# Temperature.net
KiCad netlist of a schematic drawn in EAGLE
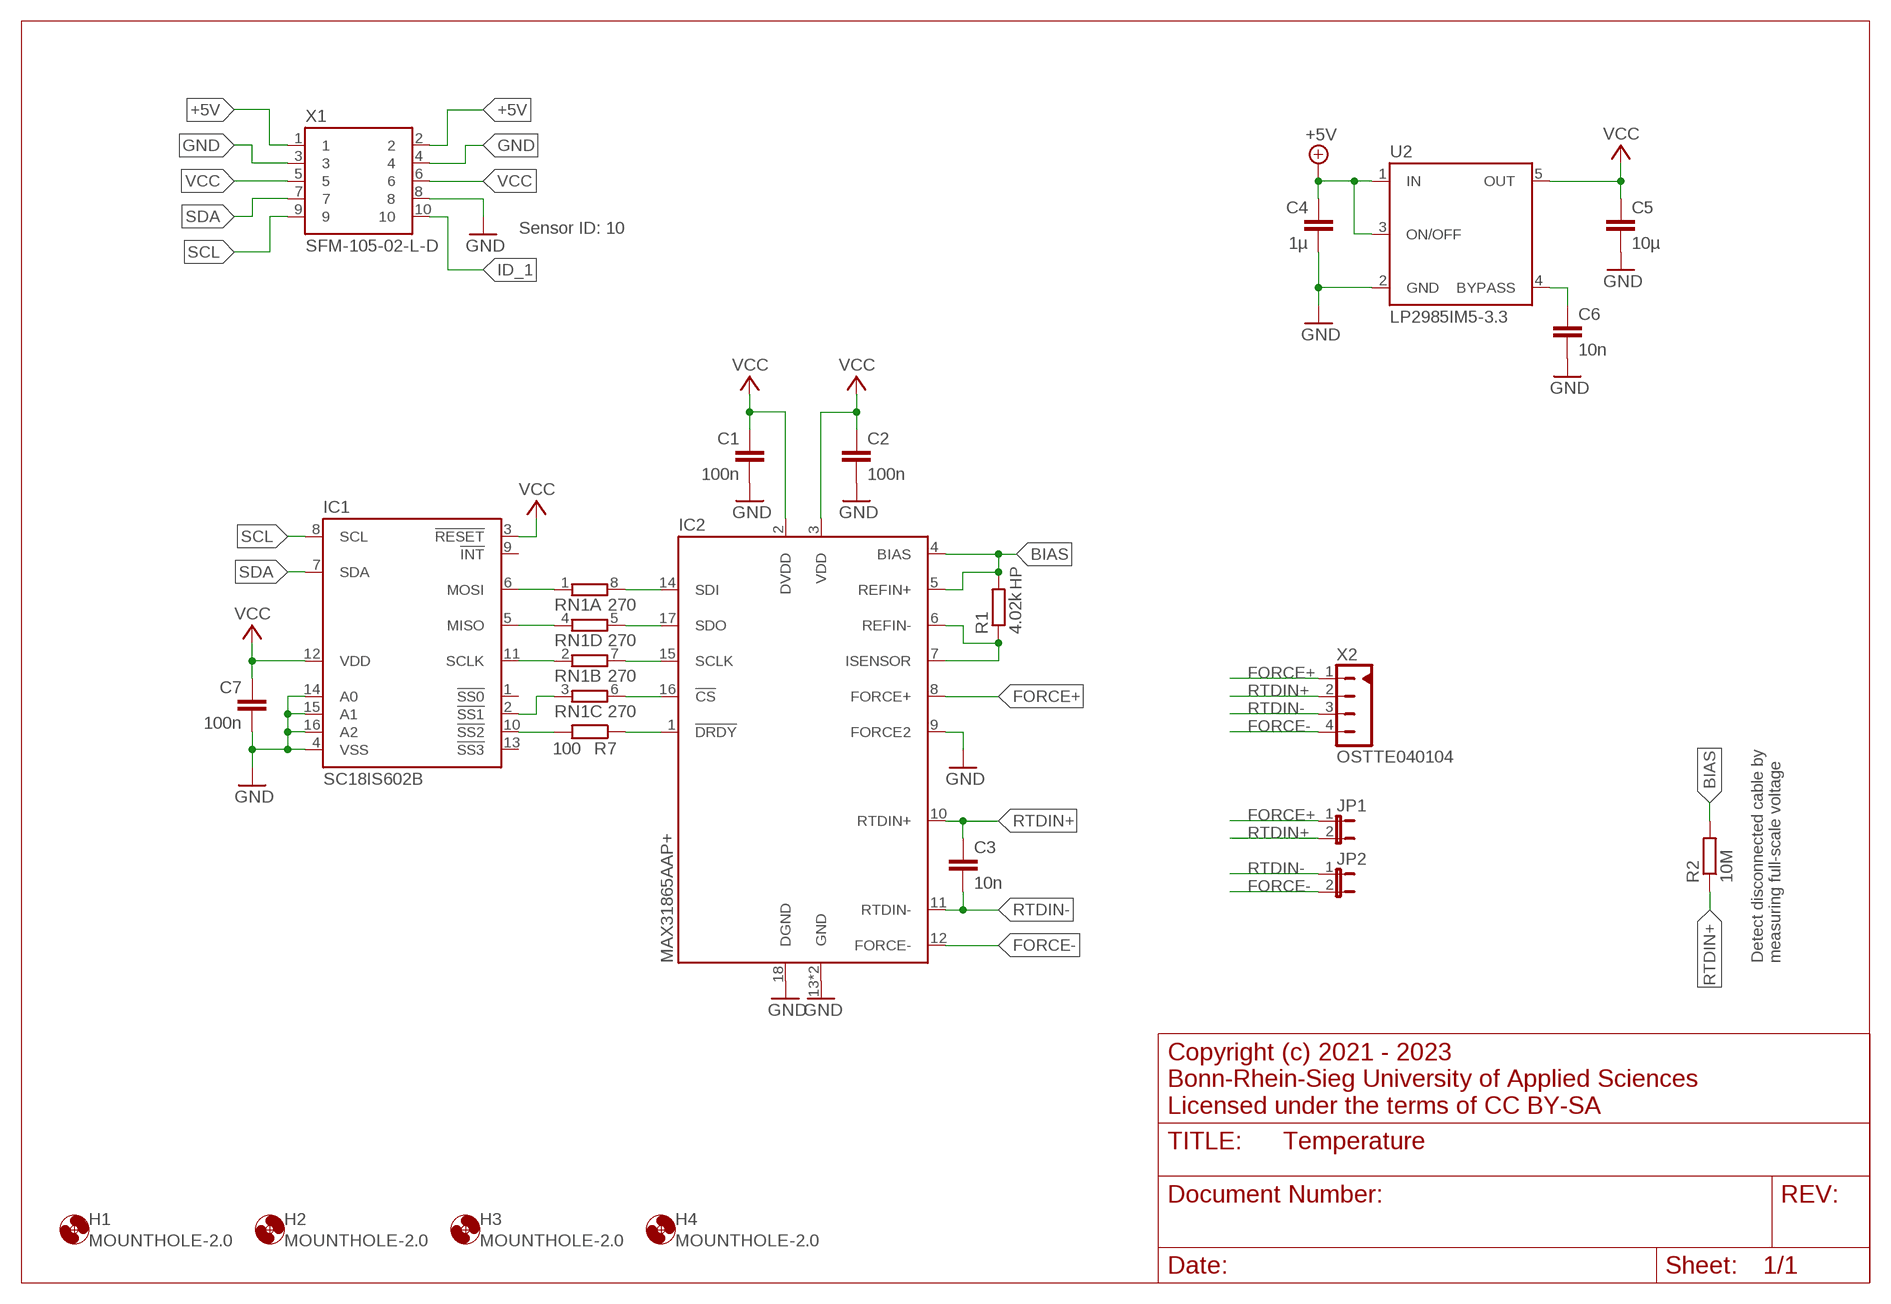
[diagram p0: schematic, sheet 1]

(export (version "E")
  (design (tool "Eeschema 10.0.6"))
  (components
    (comp (ref "C1")
      (value "100n")
      (footprint "eagle-import:C0603")
      (libsource (lib "eagle-import") (part "C-EUC0603"))
    )
    (comp (ref "C2")
      (value "100n")
      (footprint "eagle-import:C0603")
      (libsource (lib "eagle-import") (part "C-EUC0603"))
    )
    (comp (ref "C3")
      (value "10n")
      (footprint "eagle-import:C0603")
      (libsource (lib "eagle-import") (part "C-EUC0603"))
    )
    (comp (ref "C4")
      (value "1µ")
      (footprint "eagle-import:C0603")
      (libsource (lib "eagle-import") (part "C-EUC0603"))
    )
    (comp (ref "C5")
      (value "10µ")
      (footprint "eagle-import:C0603")
      (libsource (lib "eagle-import") (part "C-EUC0603"))
    )
    (comp (ref "C6")
      (value "10n")
      (footprint "eagle-import:C0603")
      (libsource (lib "eagle-import") (part "C-EUC0603"))
    )
    (comp (ref "C7")
      (value "100n")
      (footprint "eagle-import:C0603")
      (libsource (lib "eagle-import") (part "C-EUC0603"))
    )
    (comp (ref "H1")
      (value "MOUNTHOLE-2.0")
      (footprint "eagle-import:2.0")
      (libsource (lib "eagle-import") (part "MOUNTHOLE-2.0"))
    )
    (comp (ref "H2")
      (value "MOUNTHOLE-2.0")
      (footprint "eagle-import:2.0")
      (libsource (lib "eagle-import") (part "MOUNTHOLE-2.0"))
    )
    (comp (ref "H3")
      (value "MOUNTHOLE-2.0")
      (footprint "eagle-import:2.0")
      (libsource (lib "eagle-import") (part "MOUNTHOLE-2.0"))
    )
    (comp (ref "H4")
      (value "MOUNTHOLE-2.0")
      (footprint "eagle-import:2.0")
      (libsource (lib "eagle-import") (part "MOUNTHOLE-2.0"))
    )
    (comp (ref "IC1")
      (value "SC18IS602B")
      (footprint "eagle-import:TSSOP16")
      (libsource (lib "eagle-import") (part "SC18IS602B"))
    )
    (comp (ref "IC2")
      (value "MAX31865AAP+")
      (footprint "eagle-import:SSOP20")
      (libsource (lib "eagle-import") (part "MAX31865A?P+A"))
    )
    (comp (ref "JP1")
      (value "JP1E")
      (footprint "eagle-import:JP1")
      (libsource (lib "eagle-import") (part "JP1E"))
    )
    (comp (ref "JP2")
      (value "JP1E")
      (footprint "eagle-import:JP1")
      (libsource (lib "eagle-import") (part "JP1E"))
    )
    (comp (ref "R1")
      (value "4.02k")
      (footprint "eagle-import:R0603")
      (libsource (lib "eagle-import") (part "R-EU_R0603"))
    )
    (comp (ref "R2")
      (value "10M")
      (footprint "eagle-import:R0603")
      (libsource (lib "eagle-import") (part "R-EU_R0603"))
    )
    (comp (ref "R7")
      (value "100")
      (footprint "eagle-import:R0603")
      (libsource (lib "eagle-import") (part "R-EU_R0603"))
    )
    (comp (ref "RN1")
      (value "270")
      (footprint "eagle-import:EXB38V")
      (libsource (lib "eagle-import") (part "4R-NEXB38V"))
    )
    (comp (ref "U2")
      (value "LP2985IM5-3.3")
      (footprint "eagle-import:SOT23-5")
      (libsource (lib "eagle-import") (part "LP2985?-IM53.3"))
    )
    (comp (ref "X1")
      (value "SFM-105-02-L-D")
      (footprint "eagle-import:SAMTEC-SFM-105-02-L-D")
      (libsource (lib "eagle-import") (part "SFM-105-02-L-D"))
    )
    (comp (ref "X2")
      (value "OSTTE040104")
      (footprint "eagle-import:OSTTE04")
      (libsource (lib "eagle-import") (part "OSTTE040104"))
    )
  )
  (nets
    (net (code "1") (name "+5V") (class "Default")
      (node (ref "C4") (pin "1") (pinfunction "1_1") (pintype "passive"))
      (node (ref "U2") (pin "1") (pinfunction "IN_1") (pintype "bidirectional"))
      (node (ref "U2") (pin "3") (pinfunction "ON/OFF_3") (pintype "bidirectional"))
      (node (ref "X1") (pin "1") (pinfunction "1_1") (pintype "passive"))
      (node (ref "X1") (pin "2") (pinfunction "2_2") (pintype "passive"))
    )
    (net (code "2") (name "BIAS") (class "Default")
      (node (ref "IC2") (pin "4") (pinfunction "BIAS_4") (pintype "bidirectional"))
      (node (ref "IC2") (pin "5") (pinfunction "REFIN+_5") (pintype "bidirectional"))
      (node (ref "R1") (pin "2") (pinfunction "2_2") (pintype "passive"))
      (node (ref "R2") (pin "2") (pinfunction "2_2") (pintype "passive"))
    )
    (net (code "3") (name "FORCE+") (class "Default")
      (node (ref "IC2") (pin "8") (pinfunction "FORCE+_8") (pintype "bidirectional"))
      (node (ref "JP1") (pin "1") (pinfunction "1_1") (pintype "passive"))
      (node (ref "X2") (pin "1") (pinfunction "1_1") (pintype "passive"))
    )
    (net (code "4") (name "FORCE-") (class "Default")
      (node (ref "IC2") (pin "12") (pinfunction "FORCE-_12") (pintype "bidirectional"))
      (node (ref "JP2") (pin "2") (pinfunction "2_2") (pintype "passive"))
      (node (ref "X2") (pin "4") (pinfunction "4_4") (pintype "passive"))
    )
    (net (code "5") (name "GND") (class "Default")
      (node (ref "C1") (pin "2") (pinfunction "2_2") (pintype "passive"))
      (node (ref "C2") (pin "2") (pinfunction "2_2") (pintype "passive"))
      (node (ref "C4") (pin "2") (pinfunction "2_2") (pintype "passive"))
      (node (ref "C5") (pin "2") (pinfunction "2_2") (pintype "passive"))
      (node (ref "C6") (pin "2") (pinfunction "2_2") (pintype "passive"))
      (node (ref "C7") (pin "2") (pinfunction "2_2") (pintype "passive"))
      (node (ref "IC1") (pin "14") (pinfunction "A0_14") (pintype "input"))
      (node (ref "IC1") (pin "15") (pinfunction "A1_15") (pintype "input"))
      (node (ref "IC1") (pin "16") (pinfunction "A2_16") (pintype "input"))
      (node (ref "IC1") (pin "4") (pinfunction "VSS_4") (pintype "power_in"))
      (node (ref "IC2") (pin "13") (pinfunction "GND_13") (pintype "bidirectional"))
      (node (ref "IC2") (pin "18") (pinfunction "DGND_18") (pintype "bidirectional"))
      (node (ref "IC2") (pin "19") (pinfunction "GND_19") (pintype "bidirectional"))
      (node (ref "IC2") (pin "9") (pinfunction "FORCE2_9") (pintype "bidirectional"))
      (node (ref "U2") (pin "2") (pinfunction "GND_2") (pintype "bidirectional"))
      (node (ref "X1") (pin "3") (pinfunction "3_3") (pintype "passive"))
      (node (ref "X1") (pin "4") (pinfunction "4_4") (pintype "passive"))
      (node (ref "X1") (pin "8") (pinfunction "8_8") (pintype "passive"))
    )
    (net (code "6") (name "ID_1") (class "Default")
      (node (ref "X1") (pin "10") (pinfunction "10_10") (pintype "passive"))
    )
    (net (code "7") (name "Net-(IC1-MISO)") (class "Default")
      (node (ref "IC1") (pin "5") (pinfunction "MISO_5") (pintype "input"))
      (node (ref "RN1") (pin "4") (pinfunction "1_4") (pintype "passive"))
    )
    (net (code "8") (name "Net-(IC1-MOSI)") (class "Default")
      (node (ref "IC1") (pin "6") (pinfunction "MOSI_6") (pintype "output"))
      (node (ref "RN1") (pin "1") (pinfunction "1_1") (pintype "passive"))
    )
    (net (code "9") (name "Net-(IC1-SCLK)") (class "Default")
      (node (ref "IC1") (pin "11") (pinfunction "SCLK_11") (pintype "output"))
      (node (ref "RN1") (pin "2") (pinfunction "1_2") (pintype "passive"))
    )
    (net (code "10") (name "Net-(IC1-~{SS1})") (class "Default")
      (node (ref "IC1") (pin "2") (pinfunction "~{SS1}_2") (pintype "bidirectional"))
      (node (ref "RN1") (pin "3") (pinfunction "1_3") (pintype "passive"))
    )
    (net (code "11") (name "Net-(IC1-~{SS2})") (class "Default")
      (node (ref "IC1") (pin "10") (pinfunction "~{SS2}_10") (pintype "bidirectional"))
      (node (ref "R7") (pin "2") (pinfunction "2_2") (pintype "passive"))
    )
    (net (code "12") (name "Net-(IC2-ISENSOR)") (class "Default")
      (node (ref "IC2") (pin "6") (pinfunction "REFIN-_6") (pintype "bidirectional"))
      (node (ref "IC2") (pin "7") (pinfunction "ISENSOR_7") (pintype "bidirectional"))
      (node (ref "R1") (pin "1") (pinfunction "1_1") (pintype "passive"))
    )
    (net (code "13") (name "Net-(IC2-SCLK)") (class "Default")
      (node (ref "IC2") (pin "15") (pinfunction "SCLK_15") (pintype "bidirectional"))
      (node (ref "RN1") (pin "7") (pinfunction "2_7") (pintype "passive"))
    )
    (net (code "14") (name "Net-(IC2-SDI)") (class "Default")
      (node (ref "IC2") (pin "14") (pinfunction "SDI_14") (pintype "bidirectional"))
      (node (ref "RN1") (pin "8") (pinfunction "2_8") (pintype "passive"))
    )
    (net (code "15") (name "Net-(IC2-SDO)") (class "Default")
      (node (ref "IC2") (pin "17") (pinfunction "SDO_17") (pintype "bidirectional"))
      (node (ref "RN1") (pin "5") (pinfunction "2_5") (pintype "passive"))
    )
    (net (code "16") (name "Net-(IC2-~{CS})") (class "Default")
      (node (ref "IC2") (pin "16") (pinfunction "~{CS}_16") (pintype "bidirectional"))
      (node (ref "RN1") (pin "6") (pinfunction "2_6") (pintype "passive"))
    )
    (net (code "17") (name "Net-(IC2-~{DRDY})") (class "Default")
      (node (ref "IC2") (pin "1") (pinfunction "~{DRDY}_1") (pintype "bidirectional"))
      (node (ref "R7") (pin "1") (pinfunction "1_1") (pintype "passive"))
    )
    (net (code "18") (name "Net-(U2-BYPASS)") (class "Default")
      (node (ref "C6") (pin "1") (pinfunction "1_1") (pintype "passive"))
      (node (ref "U2") (pin "4") (pinfunction "BYPASS_4") (pintype "bidirectional"))
    )
    (net (code "19") (name "RTDIN+") (class "Default")
      (node (ref "C3") (pin "1") (pinfunction "1_1") (pintype "passive"))
      (node (ref "IC2") (pin "10") (pinfunction "RTDIN+_10") (pintype "bidirectional"))
      (node (ref "JP1") (pin "2") (pinfunction "2_2") (pintype "passive"))
      (node (ref "R2") (pin "1") (pinfunction "1_1") (pintype "passive"))
      (node (ref "X2") (pin "2") (pinfunction "2_2") (pintype "passive"))
    )
    (net (code "20") (name "RTDIN-") (class "Default")
      (node (ref "C3") (pin "2") (pinfunction "2_2") (pintype "passive"))
      (node (ref "IC2") (pin "11") (pinfunction "RTDIN-_11") (pintype "bidirectional"))
      (node (ref "JP2") (pin "1") (pinfunction "1_1") (pintype "passive"))
      (node (ref "X2") (pin "3") (pinfunction "3_3") (pintype "passive"))
    )
    (net (code "21") (name "SCL") (class "Default")
      (node (ref "IC1") (pin "8") (pinfunction "SCL_8") (pintype "input"))
      (node (ref "X1") (pin "9") (pinfunction "9_9") (pintype "passive"))
    )
    (net (code "22") (name "SDA") (class "Default")
      (node (ref "IC1") (pin "7") (pinfunction "SDA_7") (pintype "bidirectional"))
      (node (ref "X1") (pin "7") (pinfunction "7_7") (pintype "passive"))
    )
    (net (code "23") (name "VCC") (class "Default")
      (node (ref "C1") (pin "1") (pinfunction "1_1") (pintype "passive"))
      (node (ref "C2") (pin "1") (pinfunction "1_1") (pintype "passive"))
      (node (ref "C5") (pin "1") (pinfunction "1_1") (pintype "passive"))
      (node (ref "C7") (pin "1") (pinfunction "1_1") (pintype "passive"))
      (node (ref "IC1") (pin "12") (pinfunction "VDD_12") (pintype "power_in"))
      (node (ref "IC1") (pin "3") (pinfunction "~{RESET}_3") (pintype "input"))
      (node (ref "IC2") (pin "2") (pinfunction "DVDD_2") (pintype "bidirectional"))
      (node (ref "IC2") (pin "3") (pinfunction "VDD_3") (pintype "bidirectional"))
      (node (ref "U2") (pin "5") (pinfunction "OUT_5") (pintype "bidirectional"))
      (node (ref "X1") (pin "5") (pinfunction "5_5") (pintype "passive"))
      (node (ref "X1") (pin "6") (pinfunction "6_6") (pintype "passive"))
    )
    (net (code "24") (name "unconnected-(IC1-~{INT}-Pad9)") (class "Default")
      (node (ref "IC1") (pin "9") (pinfunction "~{INT}_9") (pintype "output"))
    )
    (net (code "25") (name "unconnected-(IC1-~{SS0}-Pad1)") (class "Default")
      (node (ref "IC1") (pin "1") (pinfunction "~{SS0}_1") (pintype "bidirectional"))
    )
    (net (code "26") (name "unconnected-(IC1-~{SS3}-Pad13)") (class "Default")
      (node (ref "IC1") (pin "13") (pinfunction "~{SS3}_13") (pintype "bidirectional"))
    )
  )
)
